# inverter-schem.net
KiCad netlist of a schematic drawn in Altium Designer
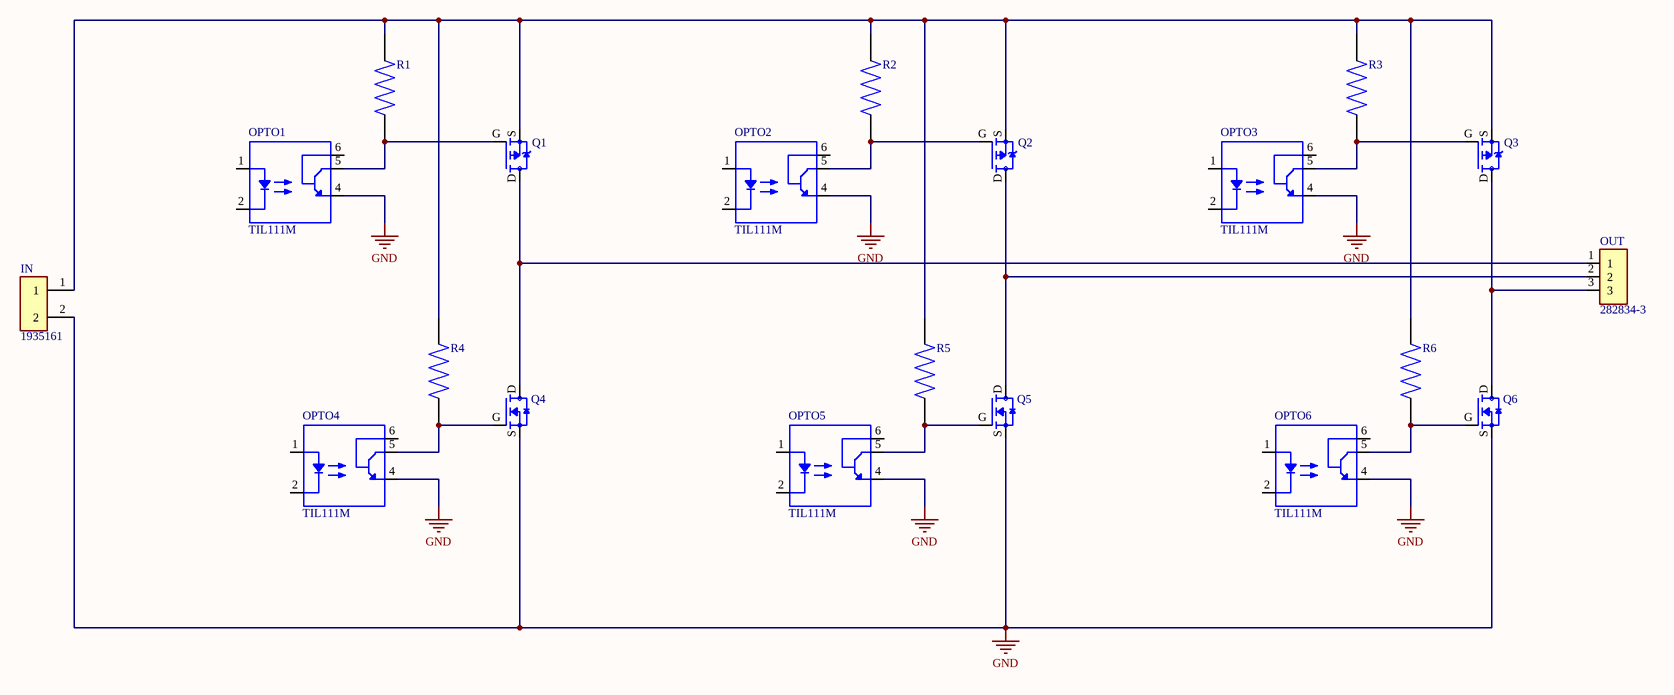
[diagram p0: inverter-schem.SchDoc]

(export (version "E")
  (design (tool "Eeschema 10.0.6"))
  (components
    (comp (ref "IN")
      (value "1935161")
      (footprint "PHOENIX_1935161")
      (description "2 Position Wire to Board Terminal Block Horizontal with Board 0.197 _5.00mm_ Through Hole")
      (fields (field (name "MF") "Phoenix Contact") (field (name "DIGI-KEY_PART_NUMBER") "277-1667-ND"))
      (libsource (lib "1935161") (part "1935161"))
    )
    (comp (ref "OPTO1")
      (value "TIL111M")
      (footprint "DIP1016W50P254L742H480Q6")
      (description "Optocoupler DC Input 1 Channel Trans W/Base DC Output 6-Pin Plastic Dip White")
      (fields (field (name "MF") "Everlight Electronics"))
      (libsource (lib "TIL111M") (part "TIL111M"))
    )
    (comp (ref "OPTO2")
      (value "TIL111M")
      (footprint "DIP1016W50P254L742H480Q6")
      (description "Optocoupler DC Input 1 Channel Trans W/Base DC Output 6-Pin Plastic Dip White")
      (fields (field (name "MF") "Everlight Electronics"))
      (libsource (lib "TIL111M") (part "TIL111M"))
    )
    (comp (ref "OPTO3")
      (value "TIL111M")
      (footprint "DIP1016W50P254L742H480Q6")
      (description "Optocoupler DC Input 1 Channel Trans W/Base DC Output 6-Pin Plastic Dip White")
      (fields (field (name "MF") "Everlight Electronics"))
      (libsource (lib "TIL111M") (part "TIL111M"))
    )
    (comp (ref "OPTO4")
      (value "TIL111M")
      (footprint "DIP1016W50P254L742H480Q6")
      (description "Optocoupler DC Input 1 Channel Trans W/Base DC Output 6-Pin Plastic Dip White")
      (fields (field (name "MF") "Everlight Electronics"))
      (libsource (lib "TIL111M") (part "TIL111M"))
    )
    (comp (ref "OPTO5")
      (value "TIL111M")
      (footprint "DIP1016W50P254L742H480Q6")
      (description "Optocoupler DC Input 1 Channel Trans W/Base DC Output 6-Pin Plastic Dip White")
      (fields (field (name "MF") "Everlight Electronics"))
      (libsource (lib "TIL111M") (part "TIL111M"))
    )
    (comp (ref "OPTO6")
      (value "TIL111M")
      (footprint "DIP1016W50P254L742H480Q6")
      (description "Optocoupler DC Input 1 Channel Trans W/Base DC Output 6-Pin Plastic Dip White")
      (fields (field (name "MF") "Everlight Electronics"))
      (libsource (lib "TIL111M") (part "TIL111M"))
    )
    (comp (ref "OUT")
      (value "282834-3")
      (footprint "TE_282834-3")
      (description "3 Position Wire to Board Terminal Block Horizontal with Board 0.100 (2.54mm)")
      (fields (field (name "MF") "TE Connectivity"))
      (libsource (lib "282834-3") (part "282834-3"))
    )
    (comp (ref "Q1")
      (value "IRF9540NSTRLPBF")
      (footprint "DPAK254P1524X483-4_3N")
      (fields (field (name "MF") "Infineon"))
      (libsource (lib "IRF9540NSTRLPBF") (part "IRF9540NSTRLPBF"))
    )
    (comp (ref "Q2")
      (value "IRF9540NSTRLPBF")
      (footprint "DPAK254P1524X483-4_3N")
      (fields (field (name "MF") "Infineon"))
      (libsource (lib "IRF9540NSTRLPBF") (part "IRF9540NSTRLPBF"))
    )
    (comp (ref "Q3")
      (value "IRF9540NSTRLPBF")
      (footprint "DPAK254P1524X483-4_3N")
      (fields (field (name "MF") "Infineon"))
      (libsource (lib "IRF9540NSTRLPBF") (part "IRF9540NSTRLPBF"))
    )
    (comp (ref "Q4")
      (value "AOD4184A")
      (footprint "DPAK228P994X240-4N")
      (description "N-Channel 40V 13A _Ta_, 50A _Tc_ 2.3W _Ta_, 50W _Tc_ Surface Mount TO-252, _D-Pak_")
      (fields (field (name "MF") "Alpha &"))
      (libsource (lib "AOD4184A") (part "AOD4184A"))
    )
    (comp (ref "Q5")
      (value "AOD4184A")
      (footprint "DPAK228P994X240-4N")
      (description "N-Channel 40V 13A _Ta_, 50A _Tc_ 2.3W _Ta_, 50W _Tc_ Surface Mount TO-252, _D-Pak_")
      (fields (field (name "MF") "Alpha &"))
      (libsource (lib "AOD4184A") (part "AOD4184A"))
    )
    (comp (ref "Q6")
      (value "AOD4184A")
      (footprint "DPAK228P994X240-4N")
      (description "N-Channel 40V 13A _Ta_, 50A _Tc_ 2.3W _Ta_, 50W _Tc_ Surface Mount TO-252, _D-Pak_")
      (fields (field (name "MF") "Alpha &"))
      (libsource (lib "AOD4184A") (part "AOD4184A"))
    )
    (comp (ref "R1")
      (value "RNCP1206FTD10K0")
      (footprint "RESC3115X60N")
      (description "RES 10K OHM 1% 1/2W 1206")
      (fields (field (name "MF") "Stackpole Electronics"))
      (libsource (lib "RNCP1206FTD10K0") (part "RNCP1206FTD10K0"))
    )
    (comp (ref "R2")
      (value "RNCP1206FTD10K0")
      (footprint "RESC3115X60N")
      (description "RES 10K OHM 1% 1/2W 1206")
      (fields (field (name "MF") "Stackpole Electronics"))
      (libsource (lib "RNCP1206FTD10K0") (part "RNCP1206FTD10K0"))
    )
    (comp (ref "R3")
      (value "RNCP1206FTD10K0")
      (footprint "RESC3115X60N")
      (description "RES 10K OHM 1% 1/2W 1206")
      (fields (field (name "MF") "Stackpole Electronics"))
      (libsource (lib "RNCP1206FTD10K0") (part "RNCP1206FTD10K0"))
    )
    (comp (ref "R4")
      (value "RNCP1206FTD10K0")
      (footprint "RESC3115X60N")
      (description "RES 10K OHM 1% 1/2W 1206")
      (fields (field (name "MF") "Stackpole Electronics"))
      (libsource (lib "RNCP1206FTD10K0") (part "RNCP1206FTD10K0"))
    )
    (comp (ref "R5")
      (value "RNCP1206FTD10K0")
      (footprint "RESC3115X60N")
      (description "RES 10K OHM 1% 1/2W 1206")
      (fields (field (name "MF") "Stackpole Electronics"))
      (libsource (lib "RNCP1206FTD10K0") (part "RNCP1206FTD10K0"))
    )
    (comp (ref "R6")
      (value "RNCP1206FTD10K0")
      (footprint "RESC3115X60N")
      (description "RES 10K OHM 1% 1/2W 1206")
      (fields (field (name "MF") "Stackpole Electronics"))
      (libsource (lib "RNCP1206FTD10K0") (part "RNCP1206FTD10K0"))
    )
  )
  (nets
    (net (code "1") (name "GND") (class "Default")
      (node (ref "IN") (pin "2") (pinfunction "2_2") (pintype "passive"))
      (node (ref "OPTO1") (pin "4") (pinfunction "EM_4") (pintype "passive"))
      (node (ref "OPTO2") (pin "4") (pinfunction "EM_4") (pintype "passive"))
      (node (ref "OPTO3") (pin "4") (pinfunction "EM_4") (pintype "passive"))
      (node (ref "OPTO4") (pin "4") (pinfunction "EM_4") (pintype "passive"))
      (node (ref "OPTO5") (pin "4") (pinfunction "EM_4") (pintype "passive"))
      (node (ref "OPTO6") (pin "4") (pinfunction "EM_4") (pintype "passive"))
      (node (ref "Q4") (pin "S") (pinfunction "S_S") (pintype "passive"))
      (node (ref "Q5") (pin "S") (pinfunction "S_S") (pintype "passive"))
      (node (ref "Q6") (pin "S") (pinfunction "S_S") (pintype "passive"))
    )
    (net (code "2") (name "Net-(IN-Pad1)") (class "Default")
      (node (ref "IN") (pin "1") (pinfunction "1_1") (pintype "passive"))
      (node (ref "Q1") (pin "S") (pinfunction "S_S") (pintype "passive"))
      (node (ref "Q2") (pin "S") (pinfunction "S_S") (pintype "passive"))
      (node (ref "Q3") (pin "S") (pinfunction "S_S") (pintype "passive"))
      (node (ref "R1") (pin "2") (pinfunction "2_2") (pintype "passive"))
      (node (ref "R2") (pin "2") (pinfunction "2_2") (pintype "passive"))
      (node (ref "R3") (pin "2") (pinfunction "2_2") (pintype "passive"))
      (node (ref "R4") (pin "2") (pinfunction "2_2") (pintype "passive"))
      (node (ref "R5") (pin "2") (pinfunction "2_2") (pintype "passive"))
      (node (ref "R6") (pin "2") (pinfunction "2_2") (pintype "passive"))
    )
    (net (code "3") (name "Net-(OPTO1-CO)") (class "Default")
      (node (ref "OPTO1") (pin "5") (pinfunction "CO_5") (pintype "passive"))
      (node (ref "Q1") (pin "G") (pinfunction "G_G") (pintype "passive"))
      (node (ref "R1") (pin "1") (pinfunction "1_1") (pintype "passive"))
    )
    (net (code "4") (name "Net-(OPTO2-CO)") (class "Default")
      (node (ref "OPTO2") (pin "5") (pinfunction "CO_5") (pintype "passive"))
      (node (ref "Q2") (pin "G") (pinfunction "G_G") (pintype "passive"))
      (node (ref "R2") (pin "1") (pinfunction "1_1") (pintype "passive"))
    )
    (net (code "5") (name "Net-(OPTO3-CO)") (class "Default")
      (node (ref "OPTO3") (pin "5") (pinfunction "CO_5") (pintype "passive"))
      (node (ref "Q3") (pin "G") (pinfunction "G_G") (pintype "passive"))
      (node (ref "R3") (pin "1") (pinfunction "1_1") (pintype "passive"))
    )
    (net (code "6") (name "Net-(OPTO4-CO)") (class "Default")
      (node (ref "OPTO4") (pin "5") (pinfunction "CO_5") (pintype "passive"))
      (node (ref "Q4") (pin "G") (pinfunction "G_G") (pintype "passive"))
      (node (ref "R4") (pin "1") (pinfunction "1_1") (pintype "passive"))
    )
    (net (code "7") (name "Net-(OPTO5-CO)") (class "Default")
      (node (ref "OPTO5") (pin "5") (pinfunction "CO_5") (pintype "passive"))
      (node (ref "Q5") (pin "G") (pinfunction "G_G") (pintype "passive"))
      (node (ref "R5") (pin "1") (pinfunction "1_1") (pintype "passive"))
    )
    (net (code "8") (name "Net-(OPTO6-CO)") (class "Default")
      (node (ref "OPTO6") (pin "5") (pinfunction "CO_5") (pintype "passive"))
      (node (ref "Q6") (pin "G") (pinfunction "G_G") (pintype "passive"))
      (node (ref "R6") (pin "1") (pinfunction "1_1") (pintype "passive"))
    )
    (net (code "9") (name "Net-(OUT-Pad1)") (class "Default")
      (node (ref "OUT") (pin "1") (pinfunction "1_1") (pintype "passive"))
      (node (ref "Q1") (pin "D") (pinfunction "D_D") (pintype "passive"))
      (node (ref "Q4") (pin "D") (pinfunction "D_D") (pintype "passive"))
    )
    (net (code "10") (name "Net-(OUT-Pad2)") (class "Default")
      (node (ref "OUT") (pin "2") (pinfunction "2_2") (pintype "passive"))
      (node (ref "Q2") (pin "D") (pinfunction "D_D") (pintype "passive"))
      (node (ref "Q5") (pin "D") (pinfunction "D_D") (pintype "passive"))
    )
    (net (code "11") (name "Net-(OUT-Pad3)") (class "Default")
      (node (ref "OUT") (pin "3") (pinfunction "3_3") (pintype "passive"))
      (node (ref "Q3") (pin "D") (pinfunction "D_D") (pintype "passive"))
      (node (ref "Q6") (pin "D") (pinfunction "D_D") (pintype "passive"))
    )
    (net (code "12") (name "unconnected-(OPTO1-A-Pad1)") (class "Default")
      (node (ref "OPTO1") (pin "1") (pinfunction "A_1") (pintype "passive"))
    )
    (net (code "13") (name "unconnected-(OPTO1-B-Pad6)") (class "Default")
      (node (ref "OPTO1") (pin "6") (pinfunction "B_6") (pintype "passive"))
    )
    (net (code "14") (name "unconnected-(OPTO1-C-Pad2)") (class "Default")
      (node (ref "OPTO1") (pin "2") (pinfunction "C_2") (pintype "passive"))
    )
    (net (code "15") (name "unconnected-(OPTO2-A-Pad1)") (class "Default")
      (node (ref "OPTO2") (pin "1") (pinfunction "A_1") (pintype "passive"))
    )
    (net (code "16") (name "unconnected-(OPTO2-B-Pad6)") (class "Default")
      (node (ref "OPTO2") (pin "6") (pinfunction "B_6") (pintype "passive"))
    )
    (net (code "17") (name "unconnected-(OPTO2-C-Pad2)") (class "Default")
      (node (ref "OPTO2") (pin "2") (pinfunction "C_2") (pintype "passive"))
    )
    (net (code "18") (name "unconnected-(OPTO3-A-Pad1)") (class "Default")
      (node (ref "OPTO3") (pin "1") (pinfunction "A_1") (pintype "passive"))
    )
    (net (code "19") (name "unconnected-(OPTO3-B-Pad6)") (class "Default")
      (node (ref "OPTO3") (pin "6") (pinfunction "B_6") (pintype "passive"))
    )
    (net (code "20") (name "unconnected-(OPTO3-C-Pad2)") (class "Default")
      (node (ref "OPTO3") (pin "2") (pinfunction "C_2") (pintype "passive"))
    )
    (net (code "21") (name "unconnected-(OPTO4-A-Pad1)") (class "Default")
      (node (ref "OPTO4") (pin "1") (pinfunction "A_1") (pintype "passive"))
    )
    (net (code "22") (name "unconnected-(OPTO4-B-Pad6)") (class "Default")
      (node (ref "OPTO4") (pin "6") (pinfunction "B_6") (pintype "passive"))
    )
    (net (code "23") (name "unconnected-(OPTO4-C-Pad2)") (class "Default")
      (node (ref "OPTO4") (pin "2") (pinfunction "C_2") (pintype "passive"))
    )
    (net (code "24") (name "unconnected-(OPTO5-A-Pad1)") (class "Default")
      (node (ref "OPTO5") (pin "1") (pinfunction "A_1") (pintype "passive"))
    )
    (net (code "25") (name "unconnected-(OPTO5-B-Pad6)") (class "Default")
      (node (ref "OPTO5") (pin "6") (pinfunction "B_6") (pintype "passive"))
    )
    (net (code "26") (name "unconnected-(OPTO5-C-Pad2)") (class "Default")
      (node (ref "OPTO5") (pin "2") (pinfunction "C_2") (pintype "passive"))
    )
    (net (code "27") (name "unconnected-(OPTO6-A-Pad1)") (class "Default")
      (node (ref "OPTO6") (pin "1") (pinfunction "A_1") (pintype "passive"))
    )
    (net (code "28") (name "unconnected-(OPTO6-B-Pad6)") (class "Default")
      (node (ref "OPTO6") (pin "6") (pinfunction "B_6") (pintype "passive"))
    )
    (net (code "29") (name "unconnected-(OPTO6-C-Pad2)") (class "Default")
      (node (ref "OPTO6") (pin "2") (pinfunction "C_2") (pintype "passive"))
    )
  )
)
